# stm32tut.net
KiCad netlist of a schematic drawn in Altium Designer
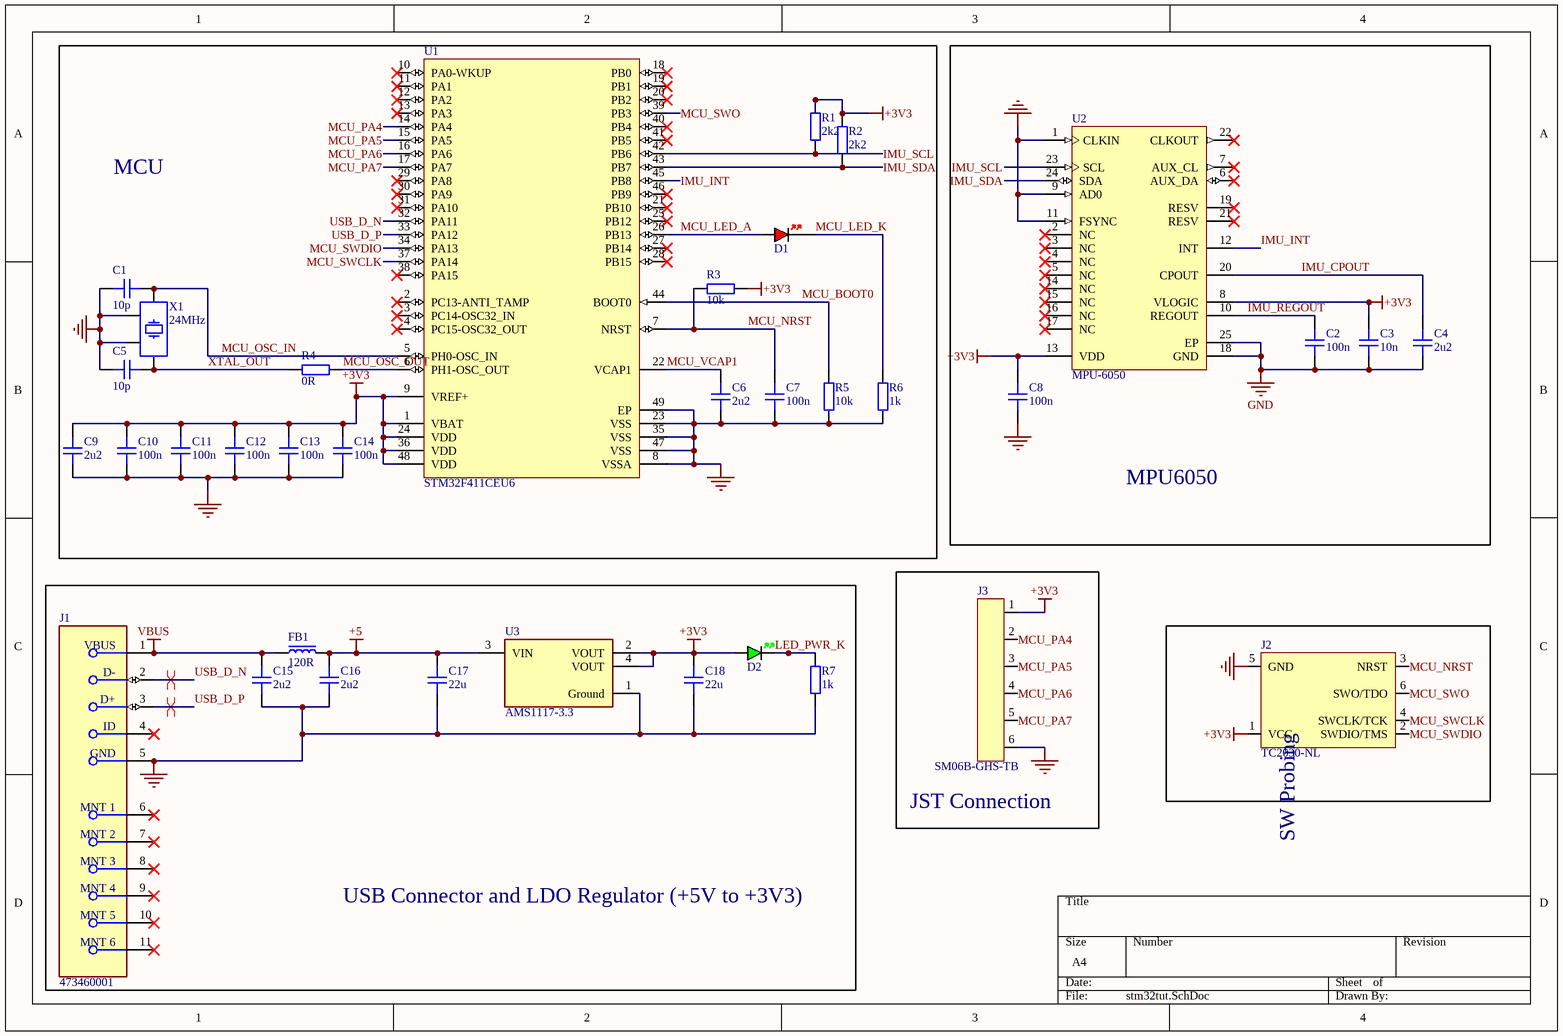
[diagram p0: stm32tut.SchDoc]

(export (version "E")
  (design (tool "Eeschema 10.0.6"))
  (components
    (comp (ref "C1")
      (value "10p")
      (footprint "CAP_0402")
      (description "Capacitor SMD 0402 16V")
      (libsource (lib "Schematic-Lib-PhilsLab") (part "CAP_0402_16V"))
    )
    (comp (ref "C2")
      (value "100n")
      (footprint "CAP_0402")
      (description "Capacitor SMD 0402 16V")
      (libsource (lib "Schematic-Lib-PhilsLab") (part "CAP_0402_16V"))
    )
    (comp (ref "C3")
      (value "10n")
      (footprint "CAP_0402")
      (description "Capacitor SMD 0402 16V")
      (libsource (lib "Schematic-Lib-PhilsLab") (part "CAP_0402_16V"))
    )
    (comp (ref "C4")
      (value "2u2")
      (footprint "CAP_0603")
      (description "Capacitor SMD 0603 16V")
      (libsource (lib "Schematic-Lib-PhilsLab") (part "CAP_0603_16V"))
    )
    (comp (ref "C5")
      (value "10p")
      (footprint "CAP_0402")
      (description "Capacitor SMD 0402 16V")
      (libsource (lib "Schematic-Lib-PhilsLab") (part "CAP_0402_16V"))
    )
    (comp (ref "C6")
      (value "2u2")
      (footprint "CAP_0603")
      (description "Capacitor SMD 0603 16V")
      (libsource (lib "Schematic-Lib-PhilsLab") (part "CAP_0603_16V"))
    )
    (comp (ref "C7")
      (value "100n")
      (footprint "CAP_0402")
      (description "Capacitor SMD 0402 16V")
      (libsource (lib "Schematic-Lib-PhilsLab") (part "CAP_0402_16V"))
    )
    (comp (ref "C8")
      (value "100n")
      (footprint "CAP_0402")
      (description "Capacitor SMD 0402 16V")
      (libsource (lib "Schematic-Lib-PhilsLab") (part "CAP_0402_16V"))
    )
    (comp (ref "C9")
      (value "2u2")
      (footprint "CAP_0603")
      (description "Capacitor SMD 0603 16V")
      (libsource (lib "Schematic-Lib-PhilsLab") (part "CAP_0603_16V"))
    )
    (comp (ref "C10")
      (value "100n")
      (footprint "CAP_0402")
      (description "Capacitor SMD 0402 16V")
      (libsource (lib "Schematic-Lib-PhilsLab") (part "CAP_0402_16V"))
    )
    (comp (ref "C11")
      (value "100n")
      (footprint "CAP_0402")
      (description "Capacitor SMD 0402 16V")
      (libsource (lib "Schematic-Lib-PhilsLab") (part "CAP_0402_16V"))
    )
    (comp (ref "C12")
      (value "100n")
      (footprint "CAP_0402")
      (description "Capacitor SMD 0402 16V")
      (libsource (lib "Schematic-Lib-PhilsLab") (part "CAP_0402_16V"))
    )
    (comp (ref "C13")
      (value "100n")
      (footprint "CAP_0402")
      (description "Capacitor SMD 0402 16V")
      (libsource (lib "Schematic-Lib-PhilsLab") (part "CAP_0402_16V"))
    )
    (comp (ref "C14")
      (value "100n")
      (footprint "CAP_0402")
      (description "Capacitor SMD 0402 16V")
      (libsource (lib "Schematic-Lib-PhilsLab") (part "CAP_0402_16V"))
    )
    (comp (ref "C15")
      (value "2u2")
      (footprint "CAP_0603")
      (description "Capacitor SMD 0603 16V")
      (libsource (lib "Schematic-Lib-PhilsLab") (part "CAP_0603_16V"))
    )
    (comp (ref "C16")
      (value "2u2")
      (footprint "CAP_0603")
      (description "Capacitor SMD 0603 16V")
      (libsource (lib "Schematic-Lib-PhilsLab") (part "CAP_0603_16V"))
    )
    (comp (ref "C17")
      (value "22u")
      (footprint "CAP_0805")
      (description "Capacitor SMD 0805 16V")
      (libsource (lib "Schematic-Lib-PhilsLab") (part "CAP_0805_16V"))
    )
    (comp (ref "C18")
      (value "22u")
      (footprint "CAP_0805")
      (description "Capacitor SMD 0805 16V")
      (libsource (lib "Schematic-Lib-PhilsLab") (part "CAP_0805_16V"))
    )
    (comp (ref "D1")
      (value "RED")
      (footprint "LED_0402_RED")
      (description "LED 0402 RED SMD")
      (libsource (lib "Schematic-Lib-PhilsLab") (part "LED_0402_RED"))
    )
    (comp (ref "D2")
      (value "GREEN")
      (footprint "LED_0402_GREEN")
      (description "LED 0402 GREEN SMD")
      (libsource (lib "Schematic-Lib-PhilsLab") (part "LED_0402_GREEN"))
    )
    (comp (ref "FB1")
      (value "120R")
      (footprint "FB_0603")
      (description "Ferrite Bead SMD 0603")
      (libsource (lib "Schematic-Lib-PhilsLab") (part "FB_0603"))
    )
    (comp (ref "J1")
      (value "473460001")
      (footprint "FP-473460001-MFG")
      (description "CONN RCPT USB2.0 MICRO B SMD R/A")
      (fields
        (field (name "OCTOPART") "https://octopart.com/47346-0001-molex-7164928")
        (field (name "MANUFACTURER") "Molex")
      )
      (libsource (lib "Altium Content Vault") (part "53ae1f1d9b557310b43ca686e5bb76a"))
    )
    (comp (ref "J2")
      (value "TC2030-NL")
      (footprint "TC2030-NL-FP")
      (description "Tag-Connect No-Solder SWD Debug Connector (No Legs) DO NOT PLACE")
      (fields
        (field (name "MANUFACTURER") "Tag-Connect")
        (field (name "MANUFACTURER PART NUMBER") "TC2030-NL-FP")
      )
      (libsource (lib "Schematic-Lib-PhilsLab") (part "TC2030-NL"))
    )
    (comp (ref "J3")
      (value "SM06B-GHS-TB")
      (footprint "SM06B-GHS-TB")
      (description "Header Connector 6 Position 1.25MM Pitch SMD Horizontal JST GH")
      (fields (field (name "MANUFACTURER") "JST"))
      (libsource (lib "Schematic-Lib-PhilsLab") (part "SM06B-GHS-TB"))
    )
    (comp (ref "R1")
      (value "2k2")
      (footprint "RES_0402")
      (description "Resistor SMD 0402")
      (libsource (lib "Schematic-Lib-PhilsLab") (part "RES_0402"))
    )
    (comp (ref "R2")
      (value "2k2")
      (footprint "RES_0402")
      (description "Resistor SMD 0402")
      (libsource (lib "Schematic-Lib-PhilsLab") (part "RES_0402"))
    )
    (comp (ref "R3")
      (value "10k")
      (footprint "RES_0402")
      (description "Resistor SMD 0402")
      (libsource (lib "Schematic-Lib-PhilsLab") (part "RES_0402"))
    )
    (comp (ref "R4")
      (value "0R")
      (footprint "RES_0402")
      (description "Resistor SMD 0402")
      (libsource (lib "Schematic-Lib-PhilsLab") (part "RES_0402"))
    )
    (comp (ref "R5")
      (value "10k")
      (footprint "RES_0402")
      (description "Resistor SMD 0402")
      (libsource (lib "Schematic-Lib-PhilsLab") (part "RES_0402"))
    )
    (comp (ref "R6")
      (value "1k")
      (footprint "RES_0402")
      (description "Resistor SMD 0402")
      (libsource (lib "Schematic-Lib-PhilsLab") (part "RES_0402"))
    )
    (comp (ref "R7")
      (value "1k")
      (footprint "RES_0402")
      (description "Resistor SMD 0402")
      (libsource (lib "Schematic-Lib-PhilsLab") (part "RES_0402"))
    )
    (comp (ref "U1")
      (value "STM32F411CEU6")
      (footprint "STM-UFQFPN48_L")
      (libsource (lib "Altium Content Vault") (part "MC-ARM-STM32F411-UFQFPN48"))
    )
    (comp (ref "U2")
      (value "MPU-6050")
      (footprint "IS-QFN-24_V")
      (fields (field (name "MANUFACTURER") "InvenSense"))
      (libsource (lib "Altium Content Vault") (part "IS-MPU-6050-QFN-24"))
    )
    (comp (ref "U3")
      (value "AMS1117-3.3")
      (footprint "FP-AMS1117-IPC_C")
      (description "LDO Voltage Regulators 1A, 3.3V")
      (fields
        (field (name "OCTOPART") "https://octopart.com/ams1117-3.3-advanced+monolithic+systems-25899300")
        (field (name "MANUFACTURER") "Advanced Monolithic Systems")
      )
      (libsource (lib "Altium Content Vault") (part "8bdbb5f8e77002000e30dd2845d0354"))
    )
    (comp (ref "X1")
      (value "24MHz")
      (footprint "XTAL_3225")
      (description "Crystal SMD 24MHz 10PPM 7pF 3225")
      (fields (field (name "MANUFACTURER") "Epson"))
      (libsource (lib "Schematic-Lib-PhilsLab") (part "TSX-3225_24.0000MF15X-AC"))
    )
  )
  (nets
    (net (code "1") (name "+3V3") (class "Default")
      (node (ref "C10") (pin "2") (pinfunction "2_2") (pintype "passive"))
      (node (ref "C11") (pin "2") (pinfunction "2_2") (pintype "passive"))
      (node (ref "C12") (pin "2") (pinfunction "2_2") (pintype "passive"))
      (node (ref "C13") (pin "2") (pinfunction "2_2") (pintype "passive"))
      (node (ref "C14") (pin "2") (pinfunction "2_2") (pintype "passive"))
      (node (ref "C18") (pin "2") (pinfunction "2_2") (pintype "passive"))
      (node (ref "C3") (pin "2") (pinfunction "2_2") (pintype "passive"))
      (node (ref "C8") (pin "1") (pinfunction "1_1") (pintype "passive"))
      (node (ref "C9") (pin "2") (pinfunction "2_2") (pintype "passive"))
      (node (ref "D2") (pin "A") (pinfunction "A_A") (pintype "passive"))
      (node (ref "J2") (pin "1") (pinfunction "VCC_1") (pintype "passive"))
      (node (ref "J3") (pin "1") (pinfunction "1_1") (pintype "passive"))
      (node (ref "R1") (pin "2") (pinfunction "2_2") (pintype "passive"))
      (node (ref "R2") (pin "2") (pinfunction "2_2") (pintype "passive"))
      (node (ref "R3") (pin "2") (pinfunction "2_2") (pintype "passive"))
      (node (ref "U1") (pin "1") (pinfunction "VBAT_1") (pintype "power_in"))
      (node (ref "U1") (pin "24") (pinfunction "VDD_24") (pintype "power_in"))
      (node (ref "U1") (pin "36") (pinfunction "VDD_36") (pintype "power_in"))
      (node (ref "U1") (pin "48") (pinfunction "VDD_48") (pintype "power_in"))
      (node (ref "U1") (pin "9") (pinfunction "VREF+_9") (pintype "power_in"))
      (node (ref "U2") (pin "13") (pinfunction "VDD_13") (pintype "power_in"))
      (node (ref "U2") (pin "8") (pinfunction "VLOGIC_8") (pintype "power_in"))
      (node (ref "U3") (pin "2") (pinfunction "VOUT_2") (pintype "passive"))
      (node (ref "U3") (pin "4") (pinfunction "VOUT_4") (pintype "passive"))
    )
    (net (code "2") (name "+5") (class "Default")
      (node (ref "C16") (pin "2") (pinfunction "2_2") (pintype "passive"))
      (node (ref "C17") (pin "2") (pinfunction "2_2") (pintype "passive"))
      (node (ref "FB1") (pin "2") (pinfunction "2_2") (pintype "passive"))
      (node (ref "U3") (pin "3") (pinfunction "VIN_3") (pintype "power_in"))
    )
    (net (code "3") (name "/IMU_CPOUT") (class "Default")
      (node (ref "C4") (pin "2") (pinfunction "2_2") (pintype "passive"))
      (node (ref "U2") (pin "20") (pinfunction "CPOUT_20") (pintype "passive"))
    )
    (net (code "4") (name "/IMU_INT") (class "Default")
      (node (ref "U1") (pin "45") (pinfunction "PB8_45") (pintype "bidirectional"))
      (node (ref "U2") (pin "12") (pinfunction "INT_12") (pintype "open_collector"))
    )
    (net (code "5") (name "/IMU_REGOUT") (class "Default")
      (node (ref "C2") (pin "2") (pinfunction "2_2") (pintype "passive"))
      (node (ref "U2") (pin "10") (pinfunction "REGOUT_10") (pintype "passive"))
    )
    (net (code "6") (name "/IMU_SCL") (class "Default")
      (node (ref "R1") (pin "1") (pinfunction "1_1") (pintype "passive"))
      (node (ref "U1") (pin "42") (pinfunction "PB6_42") (pintype "bidirectional"))
      (node (ref "U2") (pin "23") (pinfunction "SCL_23") (pintype "input"))
    )
    (net (code "7") (name "/IMU_SDA") (class "Default")
      (node (ref "R2") (pin "1") (pinfunction "1_1") (pintype "passive"))
      (node (ref "U1") (pin "43") (pinfunction "PB7_43") (pintype "bidirectional"))
      (node (ref "U2") (pin "24") (pinfunction "SDA_24") (pintype "bidirectional"))
    )
    (net (code "8") (name "/LED_PWR_K") (class "Default")
      (node (ref "D2") (pin "K") (pinfunction "K_K") (pintype "passive"))
      (node (ref "R7") (pin "2") (pinfunction "2_2") (pintype "passive"))
    )
    (net (code "9") (name "/MCU_BOOT0") (class "Default")
      (node (ref "R5") (pin "2") (pinfunction "2_2") (pintype "passive"))
      (node (ref "U1") (pin "44") (pinfunction "BOOT0_44") (pintype "input"))
    )
    (net (code "10") (name "/MCU_LED_A") (class "Default")
      (node (ref "D1") (pin "A") (pinfunction "A_A") (pintype "passive"))
      (node (ref "U1") (pin "26") (pinfunction "PB13_26") (pintype "bidirectional"))
    )
    (net (code "11") (name "/MCU_LED_K") (class "Default")
      (node (ref "D1") (pin "K") (pinfunction "K_K") (pintype "passive"))
      (node (ref "R6") (pin "2") (pinfunction "2_2") (pintype "passive"))
    )
    (net (code "12") (name "/MCU_NRST") (class "Default")
      (node (ref "C7") (pin "2") (pinfunction "2_2") (pintype "passive"))
      (node (ref "J2") (pin "3") (pinfunction "NRST_3") (pintype "passive"))
      (node (ref "R3") (pin "1") (pinfunction "1_1") (pintype "passive"))
      (node (ref "U1") (pin "7") (pinfunction "NRST_7") (pintype "bidirectional"))
    )
    (net (code "13") (name "/MCU_OSC_IN") (class "Default")
      (node (ref "C1") (pin "1") (pinfunction "1_1") (pintype "passive"))
      (node (ref "U1") (pin "5") (pinfunction "PH0-OSC_IN_5") (pintype "bidirectional"))
      (node (ref "X1") (pin "1") (pinfunction "1_1") (pintype "passive"))
    )
    (net (code "14") (name "/MCU_OSC_OUT") (class "Default")
      (node (ref "R4") (pin "2") (pinfunction "2_2") (pintype "passive"))
      (node (ref "U1") (pin "6") (pinfunction "PH1-OSC_OUT_6") (pintype "bidirectional"))
    )
    (net (code "15") (name "/MCU_PA4") (class "Default")
      (node (ref "J3") (pin "2") (pinfunction "2_2") (pintype "passive"))
      (node (ref "U1") (pin "14") (pinfunction "PA4_14") (pintype "bidirectional"))
    )
    (net (code "16") (name "/MCU_PA5") (class "Default")
      (node (ref "J3") (pin "3") (pinfunction "3_3") (pintype "passive"))
      (node (ref "U1") (pin "15") (pinfunction "PA5_15") (pintype "bidirectional"))
    )
    (net (code "17") (name "/MCU_PA6") (class "Default")
      (node (ref "J3") (pin "4") (pinfunction "4_4") (pintype "passive"))
      (node (ref "U1") (pin "16") (pinfunction "PA6_16") (pintype "bidirectional"))
    )
    (net (code "18") (name "/MCU_PA7") (class "Default")
      (node (ref "J3") (pin "5") (pinfunction "5_5") (pintype "passive"))
      (node (ref "U1") (pin "17") (pinfunction "PA7_17") (pintype "bidirectional"))
    )
    (net (code "19") (name "/MCU_SWCLK") (class "Default")
      (node (ref "J2") (pin "4") (pinfunction "SWCLK/TCK_4") (pintype "passive"))
      (node (ref "U1") (pin "37") (pinfunction "PA14_37") (pintype "bidirectional"))
    )
    (net (code "20") (name "/MCU_SWDIO") (class "Default")
      (node (ref "J2") (pin "2") (pinfunction "SWDIO/TMS_2") (pintype "passive"))
      (node (ref "U1") (pin "34") (pinfunction "PA13_34") (pintype "bidirectional"))
    )
    (net (code "21") (name "/MCU_SWO") (class "Default")
      (node (ref "J2") (pin "6") (pinfunction "SWO/TDO_6") (pintype "passive"))
      (node (ref "U1") (pin "39") (pinfunction "PB3_39") (pintype "bidirectional"))
    )
    (net (code "22") (name "/MCU_VCAP1") (class "Default")
      (node (ref "C6") (pin "2") (pinfunction "2_2") (pintype "passive"))
      (node (ref "U1") (pin "22") (pinfunction "VCAP1_22") (pintype "passive"))
    )
    (net (code "23") (name "/USB_D_N") (class "Default")
      (node (ref "J1") (pin "2") (pinfunction "D-_2") (pintype "bidirectional"))
      (node (ref "U1") (pin "32") (pinfunction "PA11_32") (pintype "bidirectional"))
    )
    (net (code "24") (name "/USB_D_P") (class "Default")
      (node (ref "J1") (pin "3") (pinfunction "D+_3") (pintype "bidirectional"))
      (node (ref "U1") (pin "33") (pinfunction "PA12_33") (pintype "bidirectional"))
    )
    (net (code "25") (name "/XTAL_OUT") (class "Default")
      (node (ref "C5") (pin "1") (pinfunction "1_1") (pintype "passive"))
      (node (ref "R4") (pin "1") (pinfunction "1_1") (pintype "passive"))
      (node (ref "X1") (pin "3") (pinfunction "3_3") (pintype "passive"))
    )
    (net (code "26") (name "GND") (class "Default")
      (node (ref "C1") (pin "2") (pinfunction "2_2") (pintype "passive"))
      (node (ref "C10") (pin "1") (pinfunction "1_1") (pintype "passive"))
      (node (ref "C11") (pin "1") (pinfunction "1_1") (pintype "passive"))
      (node (ref "C12") (pin "1") (pinfunction "1_1") (pintype "passive"))
      (node (ref "C13") (pin "1") (pinfunction "1_1") (pintype "passive"))
      (node (ref "C14") (pin "1") (pinfunction "1_1") (pintype "passive"))
      (node (ref "C15") (pin "1") (pinfunction "1_1") (pintype "passive"))
      (node (ref "C16") (pin "1") (pinfunction "1_1") (pintype "passive"))
      (node (ref "C17") (pin "1") (pinfunction "1_1") (pintype "passive"))
      (node (ref "C18") (pin "1") (pinfunction "1_1") (pintype "passive"))
      (node (ref "C2") (pin "1") (pinfunction "1_1") (pintype "passive"))
      (node (ref "C3") (pin "1") (pinfunction "1_1") (pintype "passive"))
      (node (ref "C4") (pin "1") (pinfunction "1_1") (pintype "passive"))
      (node (ref "C5") (pin "2") (pinfunction "2_2") (pintype "passive"))
      (node (ref "C6") (pin "1") (pinfunction "1_1") (pintype "passive"))
      (node (ref "C7") (pin "1") (pinfunction "1_1") (pintype "passive"))
      (node (ref "C8") (pin "2") (pinfunction "2_2") (pintype "passive"))
      (node (ref "C9") (pin "1") (pinfunction "1_1") (pintype "passive"))
      (node (ref "J1") (pin "5") (pinfunction "GND_5") (pintype "power_in"))
      (node (ref "J2") (pin "5") (pinfunction "GND_5") (pintype "passive"))
      (node (ref "J3") (pin "6") (pinfunction "6_6") (pintype "passive"))
      (node (ref "R5") (pin "1") (pinfunction "1_1") (pintype "passive"))
      (node (ref "R6") (pin "1") (pinfunction "1_1") (pintype "passive"))
      (node (ref "R7") (pin "1") (pinfunction "1_1") (pintype "passive"))
      (node (ref "U1") (pin "23") (pinfunction "VSS_23") (pintype "power_in"))
      (node (ref "U1") (pin "35") (pinfunction "VSS_35") (pintype "power_in"))
      (node (ref "U1") (pin "47") (pinfunction "VSS_47") (pintype "power_in"))
      (node (ref "U1") (pin "49") (pinfunction "EP_49") (pintype "power_in"))
      (node (ref "U1") (pin "8") (pinfunction "VSSA_8") (pintype "power_in"))
      (node (ref "U2") (pin "1") (pinfunction "CLKIN_1") (pintype "input"))
      (node (ref "U2") (pin "11") (pinfunction "FSYNC_11") (pintype "input"))
      (node (ref "U2") (pin "18") (pinfunction "GND_18") (pintype "power_in"))
      (node (ref "U2") (pin "25") (pinfunction "EP_25") (pintype "power_in"))
      (node (ref "U2") (pin "9") (pinfunction "AD0_9") (pintype "input"))
      (node (ref "U3") (pin "1") (pinfunction "Ground_1") (pintype "power_in"))
      (node (ref "X1") (pin "2") (pinfunction "2_2") (pintype "passive"))
      (node (ref "X1") (pin "4") (pinfunction "4_4") (pintype "passive"))
    )
    (net (code "27") (name "VBUS") (class "Default")
      (node (ref "C15") (pin "2") (pinfunction "2_2") (pintype "passive"))
      (node (ref "FB1") (pin "1") (pinfunction "1_1") (pintype "passive"))
      (node (ref "J1") (pin "1") (pinfunction "VBUS_1") (pintype "power_in"))
    )
    (net (code "28") (name "unconnected-(J1-ID-Pad4)") (class "Default")
      (node (ref "J1") (pin "4") (pinfunction "ID_4") (pintype "passive+no_connect"))
    )
    (net (code "29") (name "unconnected-(J1-MNT_1-Pad6)") (class "Default")
      (node (ref "J1") (pin "6") (pinfunction "MNT_1_6") (pintype "passive+no_connect"))
    )
    (net (code "30") (name "unconnected-(J1-MNT_2-Pad7)") (class "Default")
      (node (ref "J1") (pin "7") (pinfunction "MNT_2_7") (pintype "passive+no_connect"))
    )
    (net (code "31") (name "unconnected-(J1-MNT_3-Pad8)") (class "Default")
      (node (ref "J1") (pin "8") (pinfunction "MNT_3_8") (pintype "passive+no_connect"))
    )
    (net (code "32") (name "unconnected-(J1-MNT_4-Pad9)") (class "Default")
      (node (ref "J1") (pin "9") (pinfunction "MNT_4_9") (pintype "passive+no_connect"))
    )
    (net (code "33") (name "unconnected-(J1-MNT_5-Pad10)") (class "Default")
      (node (ref "J1") (pin "10") (pinfunction "MNT_5_10") (pintype "passive+no_connect"))
    )
    (net (code "34") (name "unconnected-(J1-MNT_6-Pad11)") (class "Default")
      (node (ref "J1") (pin "11") (pinfunction "MNT_6_11") (pintype "passive+no_connect"))
    )
    (net (code "35") (name "unconnected-(U1-PA0-WKUP-Pad10)") (class "Default")
      (node (ref "U1") (pin "10") (pinfunction "PA0-WKUP_10") (pintype "bidirectional+no_connect"))
    )
    (net (code "36") (name "unconnected-(U1-PA1-Pad11)") (class "Default")
      (node (ref "U1") (pin "11") (pinfunction "PA1_11") (pintype "bidirectional+no_connect"))
    )
    (net (code "37") (name "unconnected-(U1-PA2-Pad12)") (class "Default")
      (node (ref "U1") (pin "12") (pinfunction "PA2_12") (pintype "bidirectional+no_connect"))
    )
    (net (code "38") (name "unconnected-(U1-PA3-Pad13)") (class "Default")
      (node (ref "U1") (pin "13") (pinfunction "PA3_13") (pintype "bidirectional+no_connect"))
    )
    (net (code "39") (name "unconnected-(U1-PA8-Pad29)") (class "Default")
      (node (ref "U1") (pin "29") (pinfunction "PA8_29") (pintype "bidirectional+no_connect"))
    )
    (net (code "40") (name "unconnected-(U1-PA9-Pad30)") (class "Default")
      (node (ref "U1") (pin "30") (pinfunction "PA9_30") (pintype "bidirectional+no_connect"))
    )
    (net (code "41") (name "unconnected-(U1-PA10-Pad31)") (class "Default")
      (node (ref "U1") (pin "31") (pinfunction "PA10_31") (pintype "bidirectional+no_connect"))
    )
    (net (code "42") (name "unconnected-(U1-PA15-Pad38)") (class "Default")
      (node (ref "U1") (pin "38") (pinfunction "PA15_38") (pintype "bidirectional+no_connect"))
    )
    (net (code "43") (name "unconnected-(U1-PB0-Pad18)") (class "Default")
      (node (ref "U1") (pin "18") (pinfunction "PB0_18") (pintype "bidirectional+no_connect"))
    )
    (net (code "44") (name "unconnected-(U1-PB1-Pad19)") (class "Default")
      (node (ref "U1") (pin "19") (pinfunction "PB1_19") (pintype "bidirectional+no_connect"))
    )
    (net (code "45") (name "unconnected-(U1-PB2-Pad20)") (class "Default")
      (node (ref "U1") (pin "20") (pinfunction "PB2_20") (pintype "bidirectional+no_connect"))
    )
    (net (code "46") (name "unconnected-(U1-PB4-Pad40)") (class "Default")
      (node (ref "U1") (pin "40") (pinfunction "PB4_40") (pintype "bidirectional+no_connect"))
    )
    (net (code "47") (name "unconnected-(U1-PB5-Pad41)") (class "Default")
      (node (ref "U1") (pin "41") (pinfunction "PB5_41") (pintype "bidirectional+no_connect"))
    )
    (net (code "48") (name "unconnected-(U1-PB9-Pad46)") (class "Default")
      (node (ref "U1") (pin "46") (pinfunction "PB9_46") (pintype "bidirectional+no_connect"))
    )
    (net (code "49") (name "unconnected-(U1-PB10-Pad21)") (class "Default")
      (node (ref "U1") (pin "21") (pinfunction "PB10_21") (pintype "bidirectional+no_connect"))
    )
    (net (code "50") (name "unconnected-(U1-PB12-Pad25)") (class "Default")
      (node (ref "U1") (pin "25") (pinfunction "PB12_25") (pintype "bidirectional+no_connect"))
    )
    (net (code "51") (name "unconnected-(U1-PB14-Pad27)") (class "Default")
      (node (ref "U1") (pin "27") (pinfunction "PB14_27") (pintype "bidirectional+no_connect"))
    )
    (net (code "52") (name "unconnected-(U1-PB15-Pad28)") (class "Default")
      (node (ref "U1") (pin "28") (pinfunction "PB15_28") (pintype "bidirectional+no_connect"))
    )
    (net (code "53") (name "unconnected-(U1-PC13-ANTI_TAMP-Pad2)") (class "Default")
      (node (ref "U1") (pin "2") (pinfunction "PC13-ANTI_TAMP_2") (pintype "bidirectional+no_connect"))
    )
    (net (code "54") (name "unconnected-(U1-PC14-OSC32_IN-Pad3)") (class "Default")
      (node (ref "U1") (pin "3") (pinfunction "PC14-OSC32_IN_3") (pintype "bidirectional+no_connect"))
    )
    (net (code "55") (name "unconnected-(U1-PC15-OSC32_OUT-Pad4)") (class "Default")
      (node (ref "U1") (pin "4") (pinfunction "PC15-OSC32_OUT_4") (pintype "bidirectional+no_connect"))
    )
    (net (code "56") (name "unconnected-(U2-AUX_CL-Pad7)") (class "Default")
      (node (ref "U2") (pin "7") (pinfunction "AUX_CL_7") (pintype "output+no_connect"))
    )
    (net (code "57") (name "unconnected-(U2-AUX_DA-Pad6)") (class "Default")
      (node (ref "U2") (pin "6") (pinfunction "AUX_DA_6") (pintype "bidirectional+no_connect"))
    )
    (net (code "58") (name "unconnected-(U2-CLKOUT-Pad22)") (class "Default")
      (node (ref "U2") (pin "22") (pinfunction "CLKOUT_22") (pintype "output+no_connect"))
    )
    (net (code "59") (name "unconnected-(U2-NC-Pad2)") (class "Default")
      (node (ref "U2") (pin "2") (pinfunction "NC_2") (pintype "passive+no_connect"))
    )
    (net (code "60") (name "unconnected-(U2-NC-Pad3)") (class "Default")
      (node (ref "U2") (pin "3") (pinfunction "NC_3") (pintype "passive+no_connect"))
    )
    (net (code "61") (name "unconnected-(U2-NC-Pad4)") (class "Default")
      (node (ref "U2") (pin "4") (pinfunction "NC_4") (pintype "passive+no_connect"))
    )
    (net (code "62") (name "unconnected-(U2-NC-Pad5)") (class "Default")
      (node (ref "U2") (pin "5") (pinfunction "NC_5") (pintype "passive+no_connect"))
    )
    (net (code "63") (name "unconnected-(U2-NC-Pad14)") (class "Default")
      (node (ref "U2") (pin "14") (pinfunction "NC_14") (pintype "passive+no_connect"))
    )
    (net (code "64") (name "unconnected-(U2-NC-Pad15)") (class "Default")
      (node (ref "U2") (pin "15") (pinfunction "NC_15") (pintype "passive+no_connect"))
    )
    (net (code "65") (name "unconnected-(U2-NC-Pad16)") (class "Default")
      (node (ref "U2") (pin "16") (pinfunction "NC_16") (pintype "passive+no_connect"))
    )
    (net (code "66") (name "unconnected-(U2-NC-Pad17)") (class "Default")
      (node (ref "U2") (pin "17") (pinfunction "NC_17") (pintype "passive+no_connect"))
    )
    (net (code "67") (name "unconnected-(U2-RESV-Pad19)") (class "Default")
      (node (ref "U2") (pin "19") (pinfunction "RESV_19") (pintype "passive+no_connect"))
    )
    (net (code "68") (name "unconnected-(U2-RESV-Pad21)") (class "Default")
      (node (ref "U2") (pin "21") (pinfunction "RESV_21") (pintype "passive+no_connect"))
    )
  )
)
